# schema_mpb_1_1_Serial.net
KiCad netlist of a schematic drawn in EAGLE
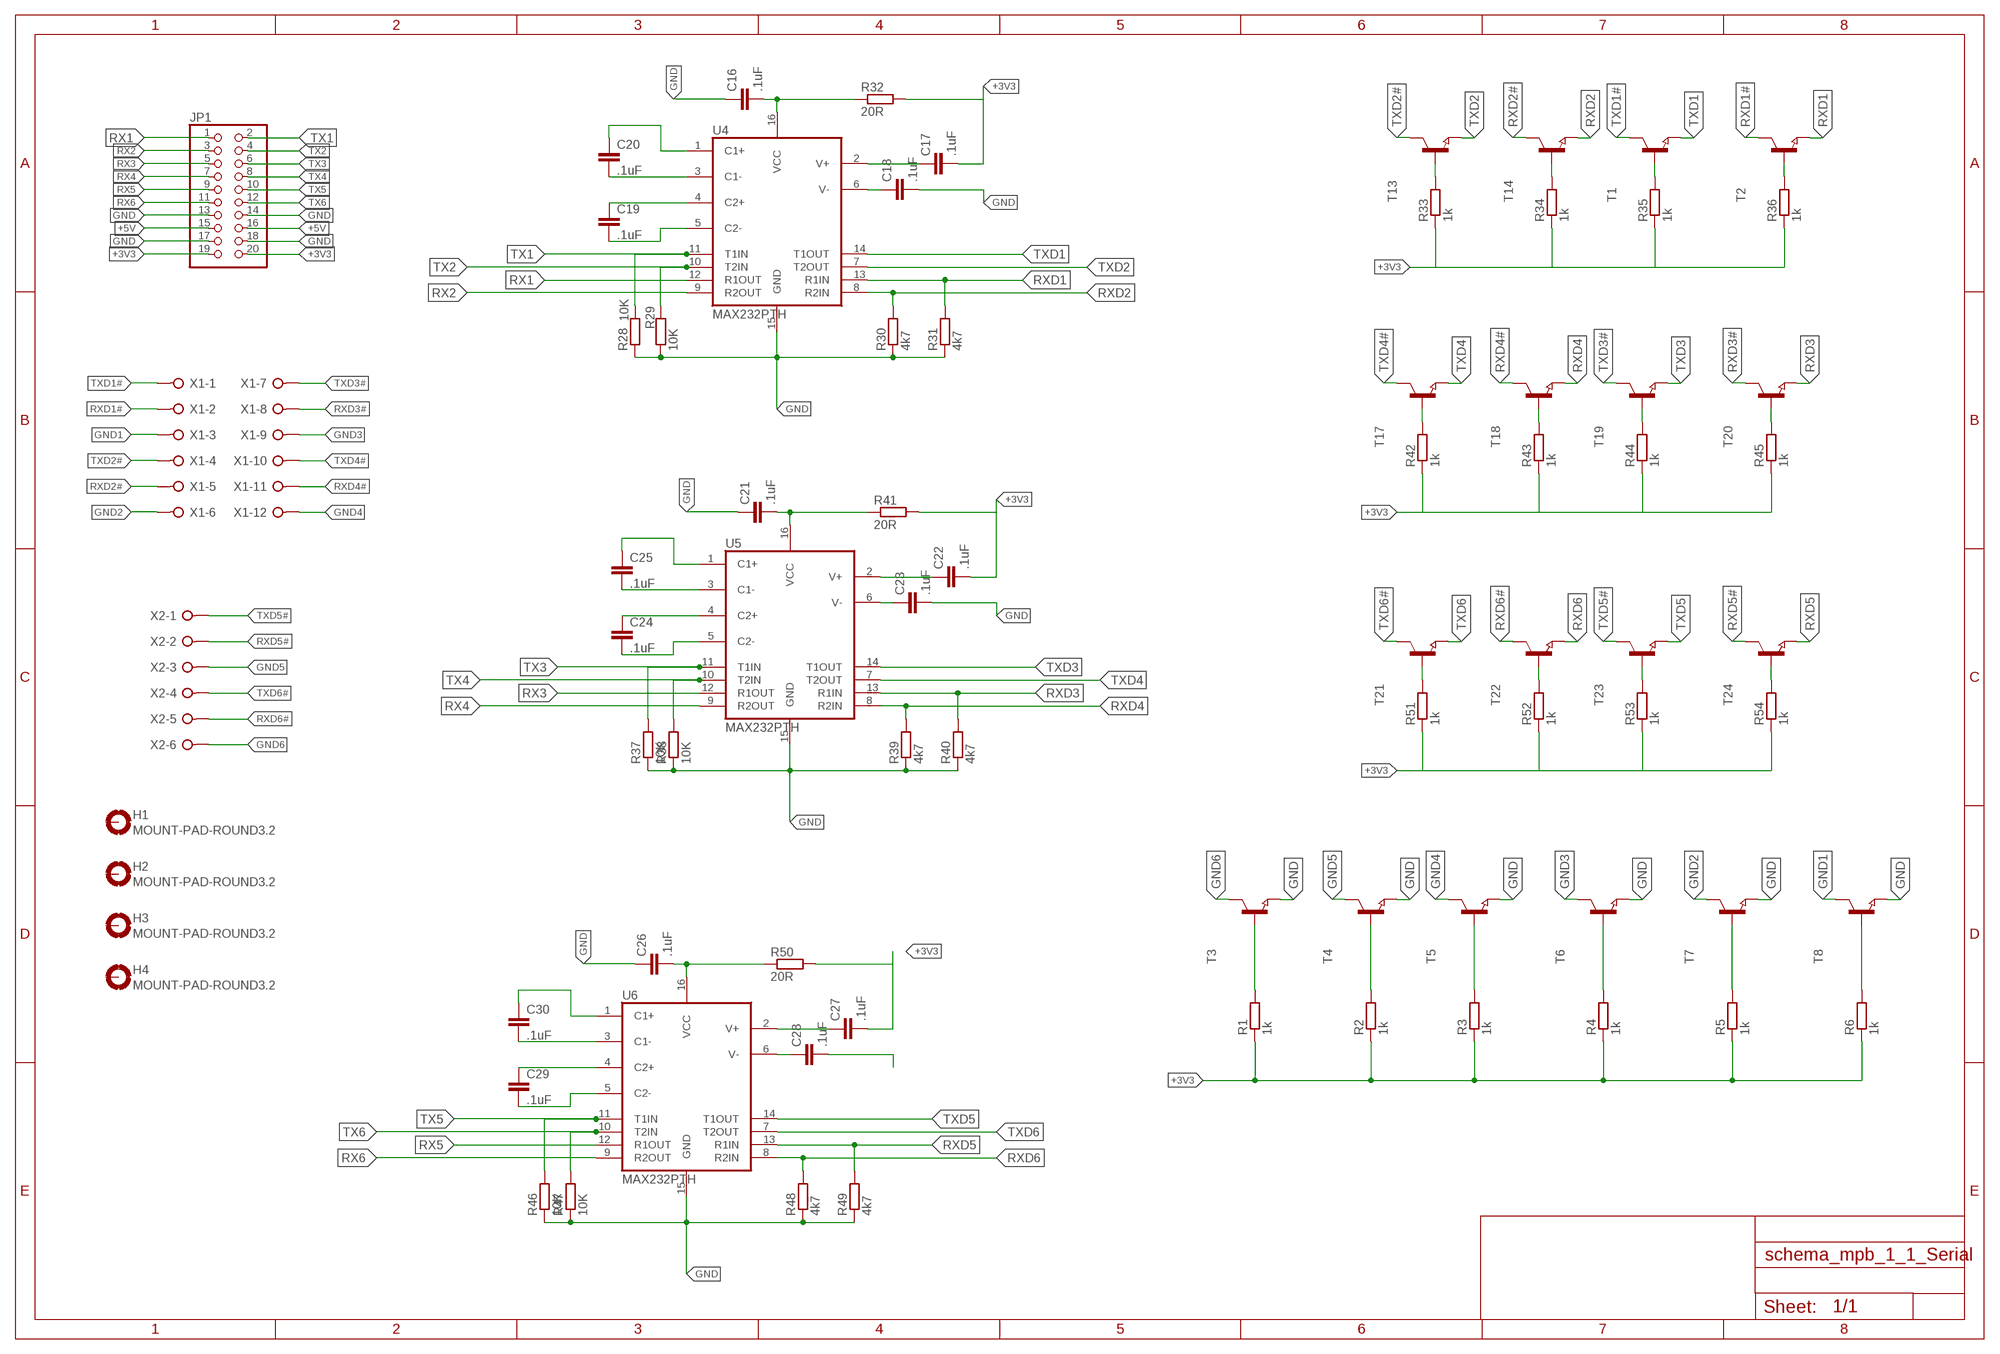
[diagram p0: schematic, sheet 1]

(export (version "E")
  (design (tool "Eeschema 10.0.6"))
  (components
    (comp (ref "C16")
      (value ".1uF")
      (footprint "eagle-import:C0603")
      (libsource (lib "eagle-import") (part "C-EUC0603"))
    )
    (comp (ref "C17")
      (value ".1uF")
      (footprint "eagle-import:C0603")
      (libsource (lib "eagle-import") (part "C-EUC0603"))
    )
    (comp (ref "C18")
      (value ".1uF")
      (footprint "eagle-import:C0603")
      (libsource (lib "eagle-import") (part "C-EUC0603"))
    )
    (comp (ref "C19")
      (value ".1uF")
      (footprint "eagle-import:C0603")
      (libsource (lib "eagle-import") (part "C-EUC0603"))
    )
    (comp (ref "C20")
      (value ".1uF")
      (footprint "eagle-import:C0603")
      (libsource (lib "eagle-import") (part "C-EUC0603"))
    )
    (comp (ref "C21")
      (value ".1uF")
      (footprint "eagle-import:C0603")
      (libsource (lib "eagle-import") (part "C-EUC0603"))
    )
    (comp (ref "C22")
      (value ".1uF")
      (footprint "eagle-import:C0603")
      (libsource (lib "eagle-import") (part "C-EUC0603"))
    )
    (comp (ref "C23")
      (value ".1uF")
      (footprint "eagle-import:C0603")
      (libsource (lib "eagle-import") (part "C-EUC0603"))
    )
    (comp (ref "C24")
      (value ".1uF")
      (footprint "eagle-import:C0603")
      (libsource (lib "eagle-import") (part "C-EUC0603"))
    )
    (comp (ref "C25")
      (value ".1uF")
      (footprint "eagle-import:C0603")
      (libsource (lib "eagle-import") (part "C-EUC0603"))
    )
    (comp (ref "C26")
      (value ".1uF")
      (footprint "eagle-import:C0603")
      (libsource (lib "eagle-import") (part "C-EUC0603"))
    )
    (comp (ref "C27")
      (value ".1uF")
      (footprint "eagle-import:C0603")
      (libsource (lib "eagle-import") (part "C-EUC0603"))
    )
    (comp (ref "C28")
      (value ".1uF")
      (footprint "eagle-import:C0603")
      (libsource (lib "eagle-import") (part "C-EUC0603"))
    )
    (comp (ref "C29")
      (value ".1uF")
      (footprint "eagle-import:C0603")
      (libsource (lib "eagle-import") (part "C-EUC0603"))
    )
    (comp (ref "C30")
      (value ".1uF")
      (footprint "eagle-import:C0603")
      (libsource (lib "eagle-import") (part "C-EUC0603"))
    )
    (comp (ref "H1")
      (value "MOUNT-PAD-ROUND3.2")
      (footprint "eagle-import:3,2-PAD")
      (libsource (lib "eagle-import") (part "MOUNT-PAD-ROUND3.2"))
    )
    (comp (ref "H2")
      (value "MOUNT-PAD-ROUND3.2")
      (footprint "eagle-import:3,2-PAD")
      (libsource (lib "eagle-import") (part "MOUNT-PAD-ROUND3.2"))
    )
    (comp (ref "H3")
      (value "MOUNT-PAD-ROUND3.2")
      (footprint "eagle-import:3,2-PAD")
      (libsource (lib "eagle-import") (part "MOUNT-PAD-ROUND3.2"))
    )
    (comp (ref "H4")
      (value "MOUNT-PAD-ROUND3.2")
      (footprint "eagle-import:3,2-PAD")
      (libsource (lib "eagle-import") (part "MOUNT-PAD-ROUND3.2"))
    )
    (comp (ref "JP1")
      (value "PINHD-2X10")
      (footprint "eagle-import:2X10")
      (libsource (lib "eagle-import") (part "PINHD-2X10"))
    )
    (comp (ref "R1")
      (value "1k")
      (footprint "eagle-import:R0603")
      (libsource (lib "eagle-import") (part "R-EU_R0603"))
    )
    (comp (ref "R2")
      (value "1k")
      (footprint "eagle-import:R0603")
      (libsource (lib "eagle-import") (part "R-EU_R0603"))
    )
    (comp (ref "R3")
      (value "1k")
      (footprint "eagle-import:R0603")
      (libsource (lib "eagle-import") (part "R-EU_R0603"))
    )
    (comp (ref "R4")
      (value "1k")
      (footprint "eagle-import:R0603")
      (libsource (lib "eagle-import") (part "R-EU_R0603"))
    )
    (comp (ref "R5")
      (value "1k")
      (footprint "eagle-import:R0603")
      (libsource (lib "eagle-import") (part "R-EU_R0603"))
    )
    (comp (ref "R6")
      (value "1k")
      (footprint "eagle-import:R0603")
      (libsource (lib "eagle-import") (part "R-EU_R0603"))
    )
    (comp (ref "R28")
      (value "10K")
      (footprint "eagle-import:R0603")
      (libsource (lib "eagle-import") (part "R-EU_R0603"))
    )
    (comp (ref "R29")
      (value "10K")
      (footprint "eagle-import:R0603")
      (libsource (lib "eagle-import") (part "R-EU_R0603"))
    )
    (comp (ref "R30")
      (value "4k7")
      (footprint "eagle-import:R0603")
      (libsource (lib "eagle-import") (part "R-EU_R0603"))
    )
    (comp (ref "R31")
      (value "4k7")
      (footprint "eagle-import:R0603")
      (libsource (lib "eagle-import") (part "R-EU_R0603"))
    )
    (comp (ref "R32")
      (value "20R")
      (footprint "eagle-import:R0603")
      (libsource (lib "eagle-import") (part "R-EU_R0603"))
    )
    (comp (ref "R33")
      (value "1k")
      (footprint "eagle-import:R0603")
      (libsource (lib "eagle-import") (part "R-EU_R0603"))
    )
    (comp (ref "R34")
      (value "1k")
      (footprint "eagle-import:R0603")
      (libsource (lib "eagle-import") (part "R-EU_R0603"))
    )
    (comp (ref "R35")
      (value "1k")
      (footprint "eagle-import:R0603")
      (libsource (lib "eagle-import") (part "R-EU_R0603"))
    )
    (comp (ref "R36")
      (value "1k")
      (footprint "eagle-import:R0603")
      (libsource (lib "eagle-import") (part "R-EU_R0603"))
    )
    (comp (ref "R37")
      (value "10K")
      (footprint "eagle-import:R0603")
      (libsource (lib "eagle-import") (part "R-EU_R0603"))
    )
    (comp (ref "R38")
      (value "10K")
      (footprint "eagle-import:R0603")
      (libsource (lib "eagle-import") (part "R-EU_R0603"))
    )
    (comp (ref "R39")
      (value "4k7")
      (footprint "eagle-import:R0603")
      (libsource (lib "eagle-import") (part "R-EU_R0603"))
    )
    (comp (ref "R40")
      (value "4k7")
      (footprint "eagle-import:R0603")
      (libsource (lib "eagle-import") (part "R-EU_R0603"))
    )
    (comp (ref "R41")
      (value "20R")
      (footprint "eagle-import:R0603")
      (libsource (lib "eagle-import") (part "R-EU_R0603"))
    )
    (comp (ref "R42")
      (value "1k")
      (footprint "eagle-import:R0603")
      (libsource (lib "eagle-import") (part "R-EU_R0603"))
    )
    (comp (ref "R43")
      (value "1k")
      (footprint "eagle-import:R0603")
      (libsource (lib "eagle-import") (part "R-EU_R0603"))
    )
    (comp (ref "R44")
      (value "1k")
      (footprint "eagle-import:R0603")
      (libsource (lib "eagle-import") (part "R-EU_R0603"))
    )
    (comp (ref "R45")
      (value "1k")
      (footprint "eagle-import:R0603")
      (libsource (lib "eagle-import") (part "R-EU_R0603"))
    )
    (comp (ref "R46")
      (value "10K")
      (footprint "eagle-import:R0603")
      (libsource (lib "eagle-import") (part "R-EU_R0603"))
    )
    (comp (ref "R47")
      (value "10K")
      (footprint "eagle-import:R0603")
      (libsource (lib "eagle-import") (part "R-EU_R0603"))
    )
    (comp (ref "R48")
      (value "4k7")
      (footprint "eagle-import:R0603")
      (libsource (lib "eagle-import") (part "R-EU_R0603"))
    )
    (comp (ref "R49")
      (value "4k7")
      (footprint "eagle-import:R0603")
      (libsource (lib "eagle-import") (part "R-EU_R0603"))
    )
    (comp (ref "R50")
      (value "20R")
      (footprint "eagle-import:R0603")
      (libsource (lib "eagle-import") (part "R-EU_R0603"))
    )
    (comp (ref "R51")
      (value "1k")
      (footprint "eagle-import:R0603")
      (libsource (lib "eagle-import") (part "R-EU_R0603"))
    )
    (comp (ref "R52")
      (value "1k")
      (footprint "eagle-import:R0603")
      (libsource (lib "eagle-import") (part "R-EU_R0603"))
    )
    (comp (ref "R53")
      (value "1k")
      (footprint "eagle-import:R0603")
      (libsource (lib "eagle-import") (part "R-EU_R0603"))
    )
    (comp (ref "R54")
      (value "1k")
      (footprint "eagle-import:R0603")
      (libsource (lib "eagle-import") (part "R-EU_R0603"))
    )
    (comp (ref "T1")
      (value "NPN-TRANSISTOR_SOT23")
      (footprint "eagle-import:SOT23")
      (libsource (lib "eagle-import") (part "NPN-TRANSISTOR_SOT23"))
    )
    (comp (ref "T2")
      (value "NPN-TRANSISTOR_SOT23")
      (footprint "eagle-import:SOT23")
      (libsource (lib "eagle-import") (part "NPN-TRANSISTOR_SOT23"))
    )
    (comp (ref "T3")
      (value "NPN-TRANSISTOR_SOT23")
      (footprint "eagle-import:SOT23")
      (libsource (lib "eagle-import") (part "NPN-TRANSISTOR_SOT23"))
    )
    (comp (ref "T4")
      (value "NPN-TRANSISTOR_SOT23")
      (footprint "eagle-import:SOT23")
      (libsource (lib "eagle-import") (part "NPN-TRANSISTOR_SOT23"))
    )
    (comp (ref "T5")
      (value "NPN-TRANSISTOR_SOT23")
      (footprint "eagle-import:SOT23")
      (libsource (lib "eagle-import") (part "NPN-TRANSISTOR_SOT23"))
    )
    (comp (ref "T6")
      (value "NPN-TRANSISTOR_SOT23")
      (footprint "eagle-import:SOT23")
      (libsource (lib "eagle-import") (part "NPN-TRANSISTOR_SOT23"))
    )
    (comp (ref "T7")
      (value "NPN-TRANSISTOR_SOT23")
      (footprint "eagle-import:SOT23")
      (libsource (lib "eagle-import") (part "NPN-TRANSISTOR_SOT23"))
    )
    (comp (ref "T8")
      (value "NPN-TRANSISTOR_SOT23")
      (footprint "eagle-import:SOT23")
      (libsource (lib "eagle-import") (part "NPN-TRANSISTOR_SOT23"))
    )
    (comp (ref "T13")
      (value "NPN-TRANSISTOR_SOT23")
      (footprint "eagle-import:SOT23")
      (libsource (lib "eagle-import") (part "NPN-TRANSISTOR_SOT23"))
    )
    (comp (ref "T14")
      (value "NPN-TRANSISTOR_SOT23")
      (footprint "eagle-import:SOT23")
      (libsource (lib "eagle-import") (part "NPN-TRANSISTOR_SOT23"))
    )
    (comp (ref "T17")
      (value "NPN-TRANSISTOR_SOT23")
      (footprint "eagle-import:SOT23")
      (libsource (lib "eagle-import") (part "NPN-TRANSISTOR_SOT23"))
    )
    (comp (ref "T18")
      (value "NPN-TRANSISTOR_SOT23")
      (footprint "eagle-import:SOT23")
      (libsource (lib "eagle-import") (part "NPN-TRANSISTOR_SOT23"))
    )
    (comp (ref "T19")
      (value "NPN-TRANSISTOR_SOT23")
      (footprint "eagle-import:SOT23")
      (libsource (lib "eagle-import") (part "NPN-TRANSISTOR_SOT23"))
    )
    (comp (ref "T20")
      (value "NPN-TRANSISTOR_SOT23")
      (footprint "eagle-import:SOT23")
      (libsource (lib "eagle-import") (part "NPN-TRANSISTOR_SOT23"))
    )
    (comp (ref "T21")
      (value "NPN-TRANSISTOR_SOT23")
      (footprint "eagle-import:SOT23")
      (libsource (lib "eagle-import") (part "NPN-TRANSISTOR_SOT23"))
    )
    (comp (ref "T22")
      (value "NPN-TRANSISTOR_SOT23")
      (footprint "eagle-import:SOT23")
      (libsource (lib "eagle-import") (part "NPN-TRANSISTOR_SOT23"))
    )
    (comp (ref "T23")
      (value "NPN-TRANSISTOR_SOT23")
      (footprint "eagle-import:SOT23")
      (libsource (lib "eagle-import") (part "NPN-TRANSISTOR_SOT23"))
    )
    (comp (ref "T24")
      (value "NPN-TRANSISTOR_SOT23")
      (footprint "eagle-import:SOT23")
      (libsource (lib "eagle-import") (part "NPN-TRANSISTOR_SOT23"))
    )
    (comp (ref "U4")
      (value "MAX232PTH")
      (footprint "eagle-import:DIL16")
      (libsource (lib "eagle-import") (part "MAX232PTH"))
    )
    (comp (ref "U5")
      (value "MAX232PTH")
      (footprint "eagle-import:DIL16")
      (libsource (lib "eagle-import") (part "MAX232PTH"))
    )
    (comp (ref "U6")
      (value "MAX232PTH")
      (footprint "eagle-import:DIL16")
      (libsource (lib "eagle-import") (part "MAX232PTH"))
    )
    (comp (ref "X1")
      (value "W237-12P")
      (footprint "eagle-import:W237-12P")
      (libsource (lib "eagle-import") (part "W237-12P"))
    )
    (comp (ref "X2")
      (value "W237-06P")
      (footprint "eagle-import:W237-6P")
      (libsource (lib "eagle-import") (part "W237-06P"))
    )
  )
  (nets
    (net (code "1") (name "+3V3") (class "Default")
      (node (ref "C17") (pin "2") (pinfunction "2_2") (pintype "passive"))
      (node (ref "C22") (pin "2") (pinfunction "2_2") (pintype "passive"))
      (node (ref "C27") (pin "2") (pinfunction "2_2") (pintype "passive"))
      (node (ref "JP1") (pin "19") (pinfunction "19_19") (pintype "passive"))
      (node (ref "JP1") (pin "20") (pinfunction "20_20") (pintype "passive"))
      (node (ref "R1") (pin "1") (pinfunction "1_1") (pintype "passive"))
      (node (ref "R2") (pin "1") (pinfunction "1_1") (pintype "passive"))
      (node (ref "R3") (pin "1") (pinfunction "1_1") (pintype "passive"))
      (node (ref "R32") (pin "2") (pinfunction "2_2") (pintype "passive"))
      (node (ref "R33") (pin "1") (pinfunction "1_1") (pintype "passive"))
      (node (ref "R34") (pin "1") (pinfunction "1_1") (pintype "passive"))
      (node (ref "R35") (pin "1") (pinfunction "1_1") (pintype "passive"))
      (node (ref "R36") (pin "1") (pinfunction "1_1") (pintype "passive"))
      (node (ref "R4") (pin "1") (pinfunction "1_1") (pintype "passive"))
      (node (ref "R41") (pin "2") (pinfunction "2_2") (pintype "passive"))
      (node (ref "R42") (pin "1") (pinfunction "1_1") (pintype "passive"))
      (node (ref "R43") (pin "1") (pinfunction "1_1") (pintype "passive"))
      (node (ref "R44") (pin "1") (pinfunction "1_1") (pintype "passive"))
      (node (ref "R45") (pin "1") (pinfunction "1_1") (pintype "passive"))
      (node (ref "R5") (pin "1") (pinfunction "1_1") (pintype "passive"))
      (node (ref "R50") (pin "2") (pinfunction "2_2") (pintype "passive"))
      (node (ref "R51") (pin "1") (pinfunction "1_1") (pintype "passive"))
      (node (ref "R52") (pin "1") (pinfunction "1_1") (pintype "passive"))
      (node (ref "R53") (pin "1") (pinfunction "1_1") (pintype "passive"))
      (node (ref "R54") (pin "1") (pinfunction "1_1") (pintype "passive"))
      (node (ref "R6") (pin "1") (pinfunction "1_1") (pintype "passive"))
    )
    (net (code "2") (name "+5V") (class "Default")
      (node (ref "JP1") (pin "15") (pinfunction "15_15") (pintype "passive"))
      (node (ref "JP1") (pin "16") (pinfunction "16_16") (pintype "passive"))
    )
    (net (code "3") (name "GND") (class "Default")
      (node (ref "C16") (pin "1") (pinfunction "1_1") (pintype "passive"))
      (node (ref "C18") (pin "2") (pinfunction "2_2") (pintype "passive"))
      (node (ref "C21") (pin "1") (pinfunction "1_1") (pintype "passive"))
      (node (ref "C23") (pin "2") (pinfunction "2_2") (pintype "passive"))
      (node (ref "C26") (pin "1") (pinfunction "1_1") (pintype "passive"))
      (node (ref "C28") (pin "2") (pinfunction "2_2") (pintype "passive"))
      (node (ref "JP1") (pin "13") (pinfunction "13_13") (pintype "passive"))
      (node (ref "JP1") (pin "14") (pinfunction "14_14") (pintype "passive"))
      (node (ref "JP1") (pin "17") (pinfunction "17_17") (pintype "passive"))
      (node (ref "JP1") (pin "18") (pinfunction "18_18") (pintype "passive"))
      (node (ref "R28") (pin "1") (pinfunction "1_1") (pintype "passive"))
      (node (ref "R29") (pin "1") (pinfunction "1_1") (pintype "passive"))
      (node (ref "R30") (pin "1") (pinfunction "1_1") (pintype "passive"))
      (node (ref "R31") (pin "1") (pinfunction "1_1") (pintype "passive"))
      (node (ref "R37") (pin "1") (pinfunction "1_1") (pintype "passive"))
      (node (ref "R38") (pin "1") (pinfunction "1_1") (pintype "passive"))
      (node (ref "R39") (pin "1") (pinfunction "1_1") (pintype "passive"))
      (node (ref "R40") (pin "1") (pinfunction "1_1") (pintype "passive"))
      (node (ref "R46") (pin "1") (pinfunction "1_1") (pintype "passive"))
      (node (ref "R47") (pin "1") (pinfunction "1_1") (pintype "passive"))
      (node (ref "R48") (pin "1") (pinfunction "1_1") (pintype "passive"))
      (node (ref "R49") (pin "1") (pinfunction "1_1") (pintype "passive"))
      (node (ref "T3") (pin "2") (pinfunction "E_2") (pintype "passive"))
      (node (ref "T4") (pin "2") (pinfunction "E_2") (pintype "passive"))
      (node (ref "T5") (pin "2") (pinfunction "E_2") (pintype "passive"))
      (node (ref "T6") (pin "2") (pinfunction "E_2") (pintype "passive"))
      (node (ref "T7") (pin "2") (pinfunction "E_2") (pintype "passive"))
      (node (ref "T8") (pin "2") (pinfunction "E_2") (pintype "passive"))
      (node (ref "U4") (pin "15") (pinfunction "GND_15") (pintype "bidirectional"))
      (node (ref "U5") (pin "15") (pinfunction "GND_15") (pintype "bidirectional"))
      (node (ref "U6") (pin "15") (pinfunction "GND_15") (pintype "bidirectional"))
    )
    (net (code "4") (name "GND1") (class "Default")
      (node (ref "T8") (pin "3") (pinfunction "C_3") (pintype "passive"))
      (node (ref "X1") (pin "3") (pinfunction "KL_3") (pintype "passive"))
    )
    (net (code "5") (name "GND2") (class "Default")
      (node (ref "T7") (pin "3") (pinfunction "C_3") (pintype "passive"))
      (node (ref "X1") (pin "6") (pinfunction "KL_6") (pintype "passive"))
    )
    (net (code "6") (name "GND3") (class "Default")
      (node (ref "T6") (pin "3") (pinfunction "C_3") (pintype "passive"))
      (node (ref "X1") (pin "9") (pinfunction "KL_9") (pintype "passive"))
    )
    (net (code "7") (name "GND4") (class "Default")
      (node (ref "T5") (pin "3") (pinfunction "C_3") (pintype "passive"))
      (node (ref "X1") (pin "12") (pinfunction "KL_12") (pintype "passive"))
    )
    (net (code "8") (name "GND5") (class "Default")
      (node (ref "T4") (pin "3") (pinfunction "C_3") (pintype "passive"))
      (node (ref "X2") (pin "3") (pinfunction "KL_3") (pintype "passive"))
    )
    (net (code "9") (name "GND6") (class "Default")
      (node (ref "T3") (pin "3") (pinfunction "C_3") (pintype "passive"))
      (node (ref "X2") (pin "6") (pinfunction "KL_6") (pintype "passive"))
    )
    (net (code "10") (name "Net-(T1-B)") (class "Default")
      (node (ref "R35") (pin "2") (pinfunction "2_2") (pintype "passive"))
      (node (ref "T1") (pin "1") (pinfunction "B_1") (pintype "passive"))
    )
    (net (code "11") (name "Net-(T2-B)") (class "Default")
      (node (ref "R36") (pin "2") (pinfunction "2_2") (pintype "passive"))
      (node (ref "T2") (pin "1") (pinfunction "B_1") (pintype "passive"))
    )
    (net (code "12") (name "Net-(T3-B)") (class "Default")
      (node (ref "R1") (pin "2") (pinfunction "2_2") (pintype "passive"))
      (node (ref "T3") (pin "1") (pinfunction "B_1") (pintype "passive"))
    )
    (net (code "13") (name "Net-(T4-B)") (class "Default")
      (node (ref "R2") (pin "2") (pinfunction "2_2") (pintype "passive"))
      (node (ref "T4") (pin "1") (pinfunction "B_1") (pintype "passive"))
    )
    (net (code "14") (name "Net-(T5-B)") (class "Default")
      (node (ref "R3") (pin "2") (pinfunction "2_2") (pintype "passive"))
      (node (ref "T5") (pin "1") (pinfunction "B_1") (pintype "passive"))
    )
    (net (code "15") (name "Net-(T6-B)") (class "Default")
      (node (ref "R4") (pin "2") (pinfunction "2_2") (pintype "passive"))
      (node (ref "T6") (pin "1") (pinfunction "B_1") (pintype "passive"))
    )
    (net (code "16") (name "Net-(T7-B)") (class "Default")
      (node (ref "R5") (pin "2") (pinfunction "2_2") (pintype "passive"))
      (node (ref "T7") (pin "1") (pinfunction "B_1") (pintype "passive"))
    )
    (net (code "17") (name "Net-(T8-B)") (class "Default")
      (node (ref "R6") (pin "2") (pinfunction "2_2") (pintype "passive"))
      (node (ref "T8") (pin "1") (pinfunction "B_1") (pintype "passive"))
    )
    (net (code "18") (name "Net-(T13-B)") (class "Default")
      (node (ref "R33") (pin "2") (pinfunction "2_2") (pintype "passive"))
      (node (ref "T13") (pin "1") (pinfunction "B_1") (pintype "passive"))
    )
    (net (code "19") (name "Net-(T14-B)") (class "Default")
      (node (ref "R34") (pin "2") (pinfunction "2_2") (pintype "passive"))
      (node (ref "T14") (pin "1") (pinfunction "B_1") (pintype "passive"))
    )
    (net (code "20") (name "Net-(T17-B)") (class "Default")
      (node (ref "R42") (pin "2") (pinfunction "2_2") (pintype "passive"))
      (node (ref "T17") (pin "1") (pinfunction "B_1") (pintype "passive"))
    )
    (net (code "21") (name "Net-(T18-B)") (class "Default")
      (node (ref "R43") (pin "2") (pinfunction "2_2") (pintype "passive"))
      (node (ref "T18") (pin "1") (pinfunction "B_1") (pintype "passive"))
    )
    (net (code "22") (name "Net-(T19-B)") (class "Default")
      (node (ref "R44") (pin "2") (pinfunction "2_2") (pintype "passive"))
      (node (ref "T19") (pin "1") (pinfunction "B_1") (pintype "passive"))
    )
    (net (code "23") (name "Net-(T20-B)") (class "Default")
      (node (ref "R45") (pin "2") (pinfunction "2_2") (pintype "passive"))
      (node (ref "T20") (pin "1") (pinfunction "B_1") (pintype "passive"))
    )
    (net (code "24") (name "Net-(T21-B)") (class "Default")
      (node (ref "R51") (pin "2") (pinfunction "2_2") (pintype "passive"))
      (node (ref "T21") (pin "1") (pinfunction "B_1") (pintype "passive"))
    )
    (net (code "25") (name "Net-(T22-B)") (class "Default")
      (node (ref "R52") (pin "2") (pinfunction "2_2") (pintype "passive"))
      (node (ref "T22") (pin "1") (pinfunction "B_1") (pintype "passive"))
    )
    (net (code "26") (name "Net-(T23-B)") (class "Default")
      (node (ref "R53") (pin "2") (pinfunction "2_2") (pintype "passive"))
      (node (ref "T23") (pin "1") (pinfunction "B_1") (pintype "passive"))
    )
    (net (code "27") (name "Net-(T24-B)") (class "Default")
      (node (ref "R54") (pin "2") (pinfunction "2_2") (pintype "passive"))
      (node (ref "T24") (pin "1") (pinfunction "B_1") (pintype "passive"))
    )
    (net (code "28") (name "Net-(U4-C1+)") (class "Default")
      (node (ref "C20") (pin "1") (pinfunction "1_1") (pintype "passive"))
      (node (ref "U4") (pin "1") (pinfunction "C1+_1") (pintype "bidirectional"))
    )
    (net (code "29") (name "Net-(U4-C1-)") (class "Default")
      (node (ref "C20") (pin "2") (pinfunction "2_2") (pintype "passive"))
      (node (ref "U4") (pin "3") (pinfunction "C1-_3") (pintype "bidirectional"))
    )
    (net (code "30") (name "Net-(U4-C2+)") (class "Default")
      (node (ref "C19") (pin "1") (pinfunction "1_1") (pintype "passive"))
      (node (ref "U4") (pin "4") (pinfunction "C2+_4") (pintype "bidirectional"))
    )
    (net (code "31") (name "Net-(U4-C2-)") (class "Default")
      (node (ref "C19") (pin "2") (pinfunction "2_2") (pintype "passive"))
      (node (ref "U4") (pin "5") (pinfunction "C2-_5") (pintype "bidirectional"))
    )
    (net (code "32") (name "Net-(U4-V+)") (class "Default")
      (node (ref "C17") (pin "1") (pinfunction "1_1") (pintype "passive"))
      (node (ref "U4") (pin "2") (pinfunction "V+_2") (pintype "bidirectional"))
    )
    (net (code "33") (name "Net-(U4-V-)") (class "Default")
      (node (ref "C18") (pin "1") (pinfunction "1_1") (pintype "passive"))
      (node (ref "U4") (pin "6") (pinfunction "V-_6") (pintype "bidirectional"))
    )
    (net (code "34") (name "Net-(U4-VCC)") (class "Default")
      (node (ref "C16") (pin "2") (pinfunction "2_2") (pintype "passive"))
      (node (ref "R32") (pin "1") (pinfunction "1_1") (pintype "passive"))
      (node (ref "U4") (pin "16") (pinfunction "VCC_16") (pintype "bidirectional"))
    )
    (net (code "35") (name "Net-(U5-C1+)") (class "Default")
      (node (ref "C25") (pin "1") (pinfunction "1_1") (pintype "passive"))
      (node (ref "U5") (pin "1") (pinfunction "C1+_1") (pintype "bidirectional"))
    )
    (net (code "36") (name "Net-(U5-C1-)") (class "Default")
      (node (ref "C25") (pin "2") (pinfunction "2_2") (pintype "passive"))
      (node (ref "U5") (pin "3") (pinfunction "C1-_3") (pintype "bidirectional"))
    )
    (net (code "37") (name "Net-(U5-C2+)") (class "Default")
      (node (ref "C24") (pin "1") (pinfunction "1_1") (pintype "passive"))
      (node (ref "U5") (pin "4") (pinfunction "C2+_4") (pintype "bidirectional"))
    )
    (net (code "38") (name "Net-(U5-C2-)") (class "Default")
      (node (ref "C24") (pin "2") (pinfunction "2_2") (pintype "passive"))
      (node (ref "U5") (pin "5") (pinfunction "C2-_5") (pintype "bidirectional"))
    )
    (net (code "39") (name "Net-(U5-V+)") (class "Default")
      (node (ref "C22") (pin "1") (pinfunction "1_1") (pintype "passive"))
      (node (ref "U5") (pin "2") (pinfunction "V+_2") (pintype "bidirectional"))
    )
    (net (code "40") (name "Net-(U5-V-)") (class "Default")
      (node (ref "C23") (pin "1") (pinfunction "1_1") (pintype "passive"))
      (node (ref "U5") (pin "6") (pinfunction "V-_6") (pintype "bidirectional"))
    )
    (net (code "41") (name "Net-(U5-VCC)") (class "Default")
      (node (ref "C21") (pin "2") (pinfunction "2_2") (pintype "passive"))
      (node (ref "R41") (pin "1") (pinfunction "1_1") (pintype "passive"))
      (node (ref "U5") (pin "16") (pinfunction "VCC_16") (pintype "bidirectional"))
    )
    (net (code "42") (name "Net-(U6-C1+)") (class "Default")
      (node (ref "C30") (pin "1") (pinfunction "1_1") (pintype "passive"))
      (node (ref "U6") (pin "1") (pinfunction "C1+_1") (pintype "bidirectional"))
    )
    (net (code "43") (name "Net-(U6-C1-)") (class "Default")
      (node (ref "C30") (pin "2") (pinfunction "2_2") (pintype "passive"))
      (node (ref "U6") (pin "3") (pinfunction "C1-_3") (pintype "bidirectional"))
    )
    (net (code "44") (name "Net-(U6-C2+)") (class "Default")
      (node (ref "C29") (pin "1") (pinfunction "1_1") (pintype "passive"))
      (node (ref "U6") (pin "4") (pinfunction "C2+_4") (pintype "bidirectional"))
    )
    (net (code "45") (name "Net-(U6-C2-)") (class "Default")
      (node (ref "C29") (pin "2") (pinfunction "2_2") (pintype "passive"))
      (node (ref "U6") (pin "5") (pinfunction "C2-_5") (pintype "bidirectional"))
    )
    (net (code "46") (name "Net-(U6-V+)") (class "Default")
      (node (ref "C27") (pin "1") (pinfunction "1_1") (pintype "passive"))
      (node (ref "U6") (pin "2") (pinfunction "V+_2") (pintype "bidirectional"))
    )
    (net (code "47") (name "Net-(U6-V-)") (class "Default")
      (node (ref "C28") (pin "1") (pinfunction "1_1") (pintype "passive"))
      (node (ref "U6") (pin "6") (pinfunction "V-_6") (pintype "bidirectional"))
    )
    (net (code "48") (name "Net-(U6-VCC)") (class "Default")
      (node (ref "C26") (pin "2") (pinfunction "2_2") (pintype "passive"))
      (node (ref "R50") (pin "1") (pinfunction "1_1") (pintype "passive"))
      (node (ref "U6") (pin "16") (pinfunction "VCC_16") (pintype "bidirectional"))
    )
    (net (code "49") (name "RX1") (class "Default")
      (node (ref "JP1") (pin "1") (pinfunction "1_1") (pintype "passive"))
      (node (ref "U4") (pin "12") (pinfunction "R1OUT_12") (pintype "output"))
    )
    (net (code "50") (name "RX2") (class "Default")
      (node (ref "JP1") (pin "3") (pinfunction "3_3") (pintype "passive"))
      (node (ref "U4") (pin "9") (pinfunction "R2OUT_9") (pintype "output"))
    )
    (net (code "51") (name "RX3") (class "Default")
      (node (ref "JP1") (pin "5") (pinfunction "5_5") (pintype "passive"))
      (node (ref "U5") (pin "12") (pinfunction "R1OUT_12") (pintype "output"))
    )
    (net (code "52") (name "RX4") (class "Default")
      (node (ref "JP1") (pin "7") (pinfunction "7_7") (pintype "passive"))
      (node (ref "U5") (pin "9") (pinfunction "R2OUT_9") (pintype "output"))
    )
    (net (code "53") (name "RX5") (class "Default")
      (node (ref "JP1") (pin "9") (pinfunction "9_9") (pintype "passive"))
      (node (ref "U6") (pin "12") (pinfunction "R1OUT_12") (pintype "output"))
    )
    (net (code "54") (name "RX6") (class "Default")
      (node (ref "JP1") (pin "11") (pinfunction "11_11") (pintype "passive"))
      (node (ref "U6") (pin "9") (pinfunction "R2OUT_9") (pintype "output"))
    )
    (net (code "55") (name "RXD1") (class "Default")
      (node (ref "R31") (pin "2") (pinfunction "2_2") (pintype "passive"))
      (node (ref "T2") (pin "2") (pinfunction "E_2") (pintype "passive"))
      (node (ref "U4") (pin "13") (pinfunction "R1IN_13") (pintype "input"))
    )
    (net (code "56") (name "RXD1#") (class "Default")
      (node (ref "T2") (pin "3") (pinfunction "C_3") (pintype "passive"))
      (node (ref "X1") (pin "2") (pinfunction "KL_2") (pintype "passive"))
    )
    (net (code "57") (name "RXD2") (class "Default")
      (node (ref "R30") (pin "2") (pinfunction "2_2") (pintype "passive"))
      (node (ref "T14") (pin "2") (pinfunction "E_2") (pintype "passive"))
      (node (ref "U4") (pin "8") (pinfunction "R2IN_8") (pintype "input"))
    )
    (net (code "58") (name "RXD2#") (class "Default")
      (node (ref "T14") (pin "3") (pinfunction "C_3") (pintype "passive"))
      (node (ref "X1") (pin "5") (pinfunction "KL_5") (pintype "passive"))
    )
    (net (code "59") (name "RXD3") (class "Default")
      (node (ref "R40") (pin "2") (pinfunction "2_2") (pintype "passive"))
      (node (ref "T20") (pin "2") (pinfunction "E_2") (pintype "passive"))
      (node (ref "U5") (pin "13") (pinfunction "R1IN_13") (pintype "input"))
    )
    (net (code "60") (name "RXD3#") (class "Default")
      (node (ref "T20") (pin "3") (pinfunction "C_3") (pintype "passive"))
      (node (ref "X1") (pin "8") (pinfunction "KL_8") (pintype "passive"))
    )
    (net (code "61") (name "RXD4") (class "Default")
      (node (ref "R39") (pin "2") (pinfunction "2_2") (pintype "passive"))
      (node (ref "T18") (pin "2") (pinfunction "E_2") (pintype "passive"))
      (node (ref "U5") (pin "8") (pinfunction "R2IN_8") (pintype "input"))
    )
    (net (code "62") (name "RXD4#") (class "Default")
      (node (ref "T18") (pin "3") (pinfunction "C_3") (pintype "passive"))
      (node (ref "X1") (pin "11") (pinfunction "KL_11") (pintype "passive"))
    )
    (net (code "63") (name "RXD5") (class "Default")
      (node (ref "R49") (pin "2") (pinfunction "2_2") (pintype "passive"))
      (node (ref "T24") (pin "2") (pinfunction "E_2") (pintype "passive"))
      (node (ref "U6") (pin "13") (pinfunction "R1IN_13") (pintype "input"))
    )
    (net (code "64") (name "RXD5#") (class "Default")
      (node (ref "T24") (pin "3") (pinfunction "C_3") (pintype "passive"))
      (node (ref "X2") (pin "2") (pinfunction "KL_2") (pintype "passive"))
    )
    (net (code "65") (name "RXD6") (class "Default")
      (node (ref "R48") (pin "2") (pinfunction "2_2") (pintype "passive"))
      (node (ref "T22") (pin "2") (pinfunction "E_2") (pintype "passive"))
      (node (ref "U6") (pin "8") (pinfunction "R2IN_8") (pintype "input"))
    )
    (net (code "66") (name "RXD6#") (class "Default")
      (node (ref "T22") (pin "3") (pinfunction "C_3") (pintype "passive"))
      (node (ref "X2") (pin "5") (pinfunction "KL_5") (pintype "passive"))
    )
    (net (code "67") (name "TX1") (class "Default")
      (node (ref "JP1") (pin "2") (pinfunction "2_2") (pintype "passive"))
      (node (ref "R28") (pin "2") (pinfunction "2_2") (pintype "passive"))
      (node (ref "U4") (pin "11") (pinfunction "T1IN_11") (pintype "input"))
    )
    (net (code "68") (name "TX2") (class "Default")
      (node (ref "JP1") (pin "4") (pinfunction "4_4") (pintype "passive"))
      (node (ref "R29") (pin "2") (pinfunction "2_2") (pintype "passive"))
      (node (ref "U4") (pin "10") (pinfunction "T2IN_10") (pintype "input"))
    )
    (net (code "69") (name "TX3") (class "Default")
      (node (ref "JP1") (pin "6") (pinfunction "6_6") (pintype "passive"))
      (node (ref "R37") (pin "2") (pinfunction "2_2") (pintype "passive"))
      (node (ref "U5") (pin "11") (pinfunction "T1IN_11") (pintype "input"))
    )
    (net (code "70") (name "TX4") (class "Default")
      (node (ref "JP1") (pin "8") (pinfunction "8_8") (pintype "passive"))
      (node (ref "R38") (pin "2") (pinfunction "2_2") (pintype "passive"))
      (node (ref "U5") (pin "10") (pinfunction "T2IN_10") (pintype "input"))
    )
    (net (code "71") (name "TX5") (class "Default")
      (node (ref "JP1") (pin "10") (pinfunction "10_10") (pintype "passive"))
      (node (ref "R46") (pin "2") (pinfunction "2_2") (pintype "passive"))
      (node (ref "U6") (pin "11") (pinfunction "T1IN_11") (pintype "input"))
    )
    (net (code "72") (name "TX6") (class "Default")
      (node (ref "JP1") (pin "12") (pinfunction "12_12") (pintype "passive"))
      (node (ref "R47") (pin "2") (pinfunction "2_2") (pintype "passive"))
      (node (ref "U6") (pin "10") (pinfunction "T2IN_10") (pintype "input"))
    )
    (net (code "73") (name "TXD1") (class "Default")
      (node (ref "T1") (pin "2") (pinfunction "E_2") (pintype "passive"))
      (node (ref "U4") (pin "14") (pinfunction "T1OUT_14") (pintype "output"))
    )
    (net (code "74") (name "TXD1#") (class "Default")
      (node (ref "T1") (pin "3") (pinfunction "C_3") (pintype "passive"))
      (node (ref "X1") (pin "1") (pinfunction "KL_1") (pintype "passive"))
    )
    (net (code "75") (name "TXD2") (class "Default")
      (node (ref "T13") (pin "2") (pinfunction "E_2") (pintype "passive"))
      (node (ref "U4") (pin "7") (pinfunction "T2OUT_7") (pintype "output"))
    )
    (net (code "76") (name "TXD2#") (class "Default")
      (node (ref "T13") (pin "3") (pinfunction "C_3") (pintype "passive"))
      (node (ref "X1") (pin "4") (pinfunction "KL_4") (pintype "passive"))
    )
    (net (code "77") (name "TXD3") (class "Default")
      (node (ref "T19") (pin "2") (pinfunction "E_2") (pintype "passive"))
      (node (ref "U5") (pin "14") (pinfunction "T1OUT_14") (pintype "output"))
    )
    (net (code "78") (name "TXD3#") (class "Default")
      (node (ref "T19") (pin "3") (pinfunction "C_3") (pintype "passive"))
      (node (ref "X1") (pin "7") (pinfunction "KL_7") (pintype "passive"))
    )
    (net (code "79") (name "TXD4") (class "Default")
      (node (ref "T17") (pin "2") (pinfunction "E_2") (pintype "passive"))
      (node (ref "U5") (pin "7") (pinfunction "T2OUT_7") (pintype "output"))
    )
    (net (code "80") (name "TXD4#") (class "Default")
      (node (ref "T17") (pin "3") (pinfunction "C_3") (pintype "passive"))
      (node (ref "X1") (pin "10") (pinfunction "KL_10") (pintype "passive"))
    )
    (net (code "81") (name "TXD5") (class "Default")
      (node (ref "T23") (pin "2") (pinfunction "E_2") (pintype "passive"))
      (node (ref "U6") (pin "14") (pinfunction "T1OUT_14") (pintype "output"))
    )
    (net (code "82") (name "TXD5#") (class "Default")
      (node (ref "T23") (pin "3") (pinfunction "C_3") (pintype "passive"))
      (node (ref "X2") (pin "1") (pinfunction "KL_1") (pintype "passive"))
    )
    (net (code "83") (name "TXD6") (class "Default")
      (node (ref "T21") (pin "2") (pinfunction "E_2") (pintype "passive"))
      (node (ref "U6") (pin "7") (pinfunction "T2OUT_7") (pintype "output"))
    )
    (net (code "84") (name "TXD6#") (class "Default")
      (node (ref "T21") (pin "3") (pinfunction "C_3") (pintype "passive"))
      (node (ref "X2") (pin "4") (pinfunction "KL_4") (pintype "passive"))
    )
    (net (code "85") (name "unconnected-(H1-MOUNT-PadB3,2)") (class "Default")
      (node (ref "H1") (pin "B3,2") (pinfunction "MOUNT_B3,2") (pintype "passive"))
    )
    (net (code "86") (name "unconnected-(H2-MOUNT-PadB3,2)") (class "Default")
      (node (ref "H2") (pin "B3,2") (pinfunction "MOUNT_B3,2") (pintype "passive"))
    )
    (net (code "87") (name "unconnected-(H3-MOUNT-PadB3,2)") (class "Default")
      (node (ref "H3") (pin "B3,2") (pinfunction "MOUNT_B3,2") (pintype "passive"))
    )
    (net (code "88") (name "unconnected-(H4-MOUNT-PadB3,2)") (class "Default")
      (node (ref "H4") (pin "B3,2") (pinfunction "MOUNT_B3,2") (pintype "passive"))
    )
  )
)
